# rev1-dragonfly.net
KiCad netlist of a schematic drawn in EAGLE
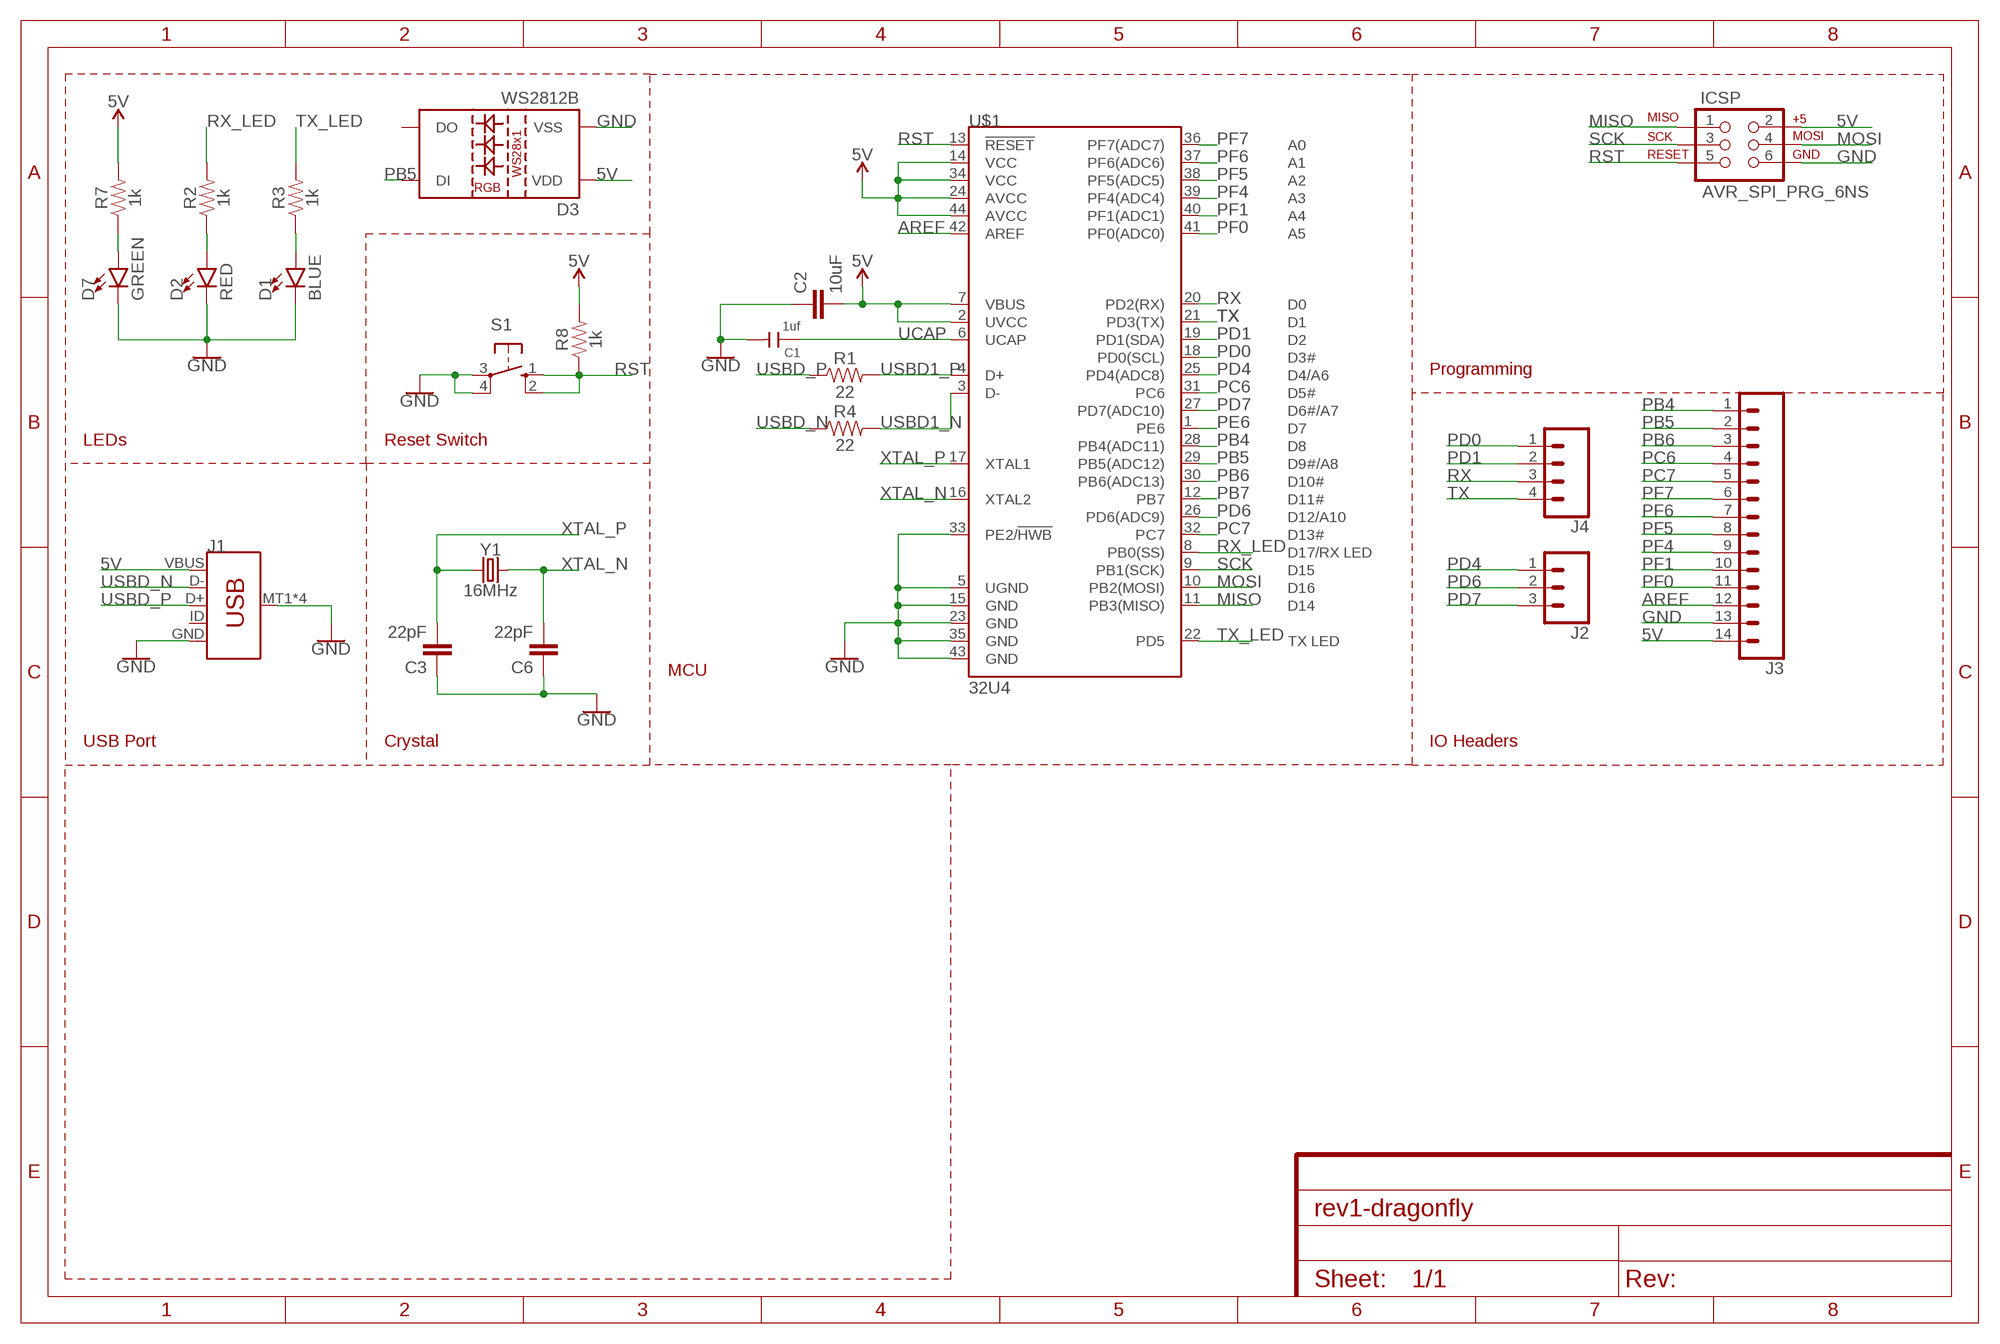
[diagram p0: schematic, sheet 1]

(export (version "E")
  (design (tool "Eeschema 10.0.6"))
  (components
    (comp (ref "C1")
      (value "1uf")
      (footprint "eagle-import:C0603")
      (fields (field (name "MPN") "CC0603KRX7R8BB105"))
      (libsource (lib "eagle-import") (part "CERAMIC-1UF-25V-10%-X7R(0603)"))
    )
    (comp (ref "C2")
      (value "10uF")
      (footprint "eagle-import:0805")
      (libsource (lib "eagle-import") (part "10UF-0805-10V-10%"))
    )
    (comp (ref "C3")
      (value "22pF")
      (footprint "eagle-import:0603")
      (libsource (lib "eagle-import") (part "22PF-0603-50V-5%"))
    )
    (comp (ref "C6")
      (value "22pF")
      (footprint "eagle-import:0603")
      (libsource (lib "eagle-import") (part "22PF-0603-50V-5%"))
    )
    (comp (ref "D1")
      (value "BLUE")
      (footprint "eagle-import:LED-0603")
      (libsource (lib "eagle-import") (part "LED-BLUE0603"))
    )
    (comp (ref "D2")
      (value "RED")
      (footprint "eagle-import:LED-0603")
      (libsource (lib "eagle-import") (part "LED-RED0603"))
    )
    (comp (ref "D3")
      (value "WS2812B")
      (footprint "eagle-import:WS2812B")
      (libsource (lib "eagle-import") (part "WS2812B"))
    )
    (comp (ref "D7")
      (value "GREEN")
      (footprint "eagle-import:LED-0603")
      (libsource (lib "eagle-import") (part "LED-GREEN0603"))
    )
    (comp (ref "ICSP")
      (value "AVR_SPI_PRG_6NS")
      (footprint "eagle-import:2X3-NS")
      (libsource (lib "eagle-import") (part "AVR_SPI_PRG_6NS"))
    )
    (comp (ref "J1")
      (value "USB_MICRO-B_SMT")
      (footprint "eagle-import:USB-MICROB")
      (libsource (lib "eagle-import") (part "USB_MICRO-B_SMT"))
    )
    (comp (ref "J2")
      (value "CONN_03")
      (footprint "eagle-import:1X03")
      (libsource (lib "eagle-import") (part "CONN_03"))
    )
    (comp (ref "J3")
      (value "CONN_14")
      (footprint "eagle-import:1X14")
      (libsource (lib "eagle-import") (part "CONN_14"))
    )
    (comp (ref "J4")
      (value "CONN_04")
      (footprint "eagle-import:1X04")
      (libsource (lib "eagle-import") (part "CONN_04"))
    )
    (comp (ref "R1")
      (value "22")
      (footprint "eagle-import:0603")
      (libsource (lib "eagle-import") (part "22OHM-0603-1/10W-1%"))
    )
    (comp (ref "R2")
      (value "1k")
      (footprint "eagle-import:0805")
      (libsource (lib "eagle-import") (part "RESISTOR0805"))
    )
    (comp (ref "R3")
      (value "1k")
      (footprint "eagle-import:0805")
      (libsource (lib "eagle-import") (part "RESISTOR0805"))
    )
    (comp (ref "R4")
      (value "22")
      (footprint "eagle-import:0603")
      (libsource (lib "eagle-import") (part "22OHM-0603-1/10W-1%"))
    )
    (comp (ref "R7")
      (value "1k")
      (footprint "eagle-import:0805")
      (libsource (lib "eagle-import") (part "RESISTOR0805"))
    )
    (comp (ref "R8")
      (value "1k")
      (footprint "eagle-import:0805")
      (libsource (lib "eagle-import") (part "RESISTOR0805"))
    )
    (comp (ref "S1")
      (value "10-XX")
      (footprint "eagle-import:B3F-10XX")
      (fields (field (name "MPN") "B3F-1000"))
      (libsource (lib "eagle-import") (part "10-XX"))
    )
    (comp (ref "U$1")
      (value "32U4")
      (footprint "eagle-import:TQFP44")
      (libsource (lib "eagle-import") (part "ATMEGA32U4TQFP-44"))
    )
    (comp (ref "Y1")
      (value "16MHz")
      (footprint "eagle-import:HC49US")
      (libsource (lib "eagle-import") (part "CRYSTAL-16MHZPTH-HC49US"))
    )
  )
  (nets
    (net (code "1") (name "/AREF") (class "Default")
      (node (ref "J3") (pin "12") (pinfunction "12_12") (pintype "passive"))
      (node (ref "U$1") (pin "42") (pinfunction "AREF_42") (pintype "bidirectional"))
    )
    (net (code "2") (name "/MISO") (class "Default")
      (node (ref "ICSP") (pin "1") (pinfunction "1_1") (pintype "passive"))
      (node (ref "U$1") (pin "11") (pinfunction "PB3(MISO)_11") (pintype "bidirectional"))
    )
    (net (code "3") (name "/MOSI") (class "Default")
      (node (ref "ICSP") (pin "4") (pinfunction "4_4") (pintype "passive"))
      (node (ref "U$1") (pin "10") (pinfunction "PB2(MOSI)_10") (pintype "bidirectional"))
    )
    (net (code "4") (name "/PB4") (class "Default")
      (node (ref "J3") (pin "1") (pinfunction "1_1") (pintype "passive"))
      (node (ref "U$1") (pin "28") (pinfunction "PB4(ADC11)_28") (pintype "bidirectional"))
    )
    (net (code "5") (name "/PB5") (class "Default")
      (node (ref "D3") (pin "4") (pinfunction "DI_4") (pintype "bidirectional"))
      (node (ref "J3") (pin "2") (pinfunction "2_2") (pintype "passive"))
      (node (ref "U$1") (pin "29") (pinfunction "PB5(ADC12)_29") (pintype "bidirectional"))
    )
    (net (code "6") (name "/PB6") (class "Default")
      (node (ref "J3") (pin "3") (pinfunction "3_3") (pintype "passive"))
      (node (ref "U$1") (pin "30") (pinfunction "PB6(ADC13)_30") (pintype "bidirectional"))
    )
    (net (code "7") (name "/PB7") (class "Default")
      (node (ref "U$1") (pin "12") (pinfunction "PB7_12") (pintype "bidirectional"))
    )
    (net (code "8") (name "/PC6") (class "Default")
      (node (ref "J3") (pin "4") (pinfunction "4_4") (pintype "passive"))
      (node (ref "U$1") (pin "31") (pinfunction "PC6_31") (pintype "bidirectional"))
    )
    (net (code "9") (name "/PC7") (class "Default")
      (node (ref "J3") (pin "5") (pinfunction "5_5") (pintype "passive"))
      (node (ref "U$1") (pin "32") (pinfunction "PC7_32") (pintype "bidirectional"))
    )
    (net (code "10") (name "/PD0") (class "Default")
      (node (ref "J4") (pin "1") (pinfunction "1_1") (pintype "passive"))
      (node (ref "U$1") (pin "18") (pinfunction "PD0(SCL)_18") (pintype "bidirectional"))
    )
    (net (code "11") (name "/PD1") (class "Default")
      (node (ref "J4") (pin "2") (pinfunction "2_2") (pintype "passive"))
      (node (ref "U$1") (pin "19") (pinfunction "PD1(SDA)_19") (pintype "bidirectional"))
    )
    (net (code "12") (name "/PD4") (class "Default")
      (node (ref "J2") (pin "1") (pinfunction "1_1") (pintype "passive"))
      (node (ref "U$1") (pin "25") (pinfunction "PD4(ADC8)_25") (pintype "bidirectional"))
    )
    (net (code "13") (name "/PD6") (class "Default")
      (node (ref "J2") (pin "2") (pinfunction "2_2") (pintype "passive"))
      (node (ref "U$1") (pin "26") (pinfunction "PD6(ADC9)_26") (pintype "bidirectional"))
    )
    (net (code "14") (name "/PD7") (class "Default")
      (node (ref "J2") (pin "3") (pinfunction "3_3") (pintype "passive"))
      (node (ref "U$1") (pin "27") (pinfunction "PD7(ADC10)_27") (pintype "bidirectional"))
    )
    (net (code "15") (name "/PE6") (class "Default")
      (node (ref "U$1") (pin "1") (pinfunction "PE6_1") (pintype "bidirectional"))
    )
    (net (code "16") (name "/PF0") (class "Default")
      (node (ref "J3") (pin "11") (pinfunction "11_11") (pintype "passive"))
      (node (ref "U$1") (pin "41") (pinfunction "PF0(ADC0)_41") (pintype "bidirectional"))
    )
    (net (code "17") (name "/PF1") (class "Default")
      (node (ref "J3") (pin "10") (pinfunction "10_10") (pintype "passive"))
      (node (ref "U$1") (pin "40") (pinfunction "PF1(ADC1)_40") (pintype "bidirectional"))
    )
    (net (code "18") (name "/PF4") (class "Default")
      (node (ref "J3") (pin "9") (pinfunction "9_9") (pintype "passive"))
      (node (ref "U$1") (pin "39") (pinfunction "PF4(ADC4)_39") (pintype "bidirectional"))
    )
    (net (code "19") (name "/PF5") (class "Default")
      (node (ref "J3") (pin "8") (pinfunction "8_8") (pintype "passive"))
      (node (ref "U$1") (pin "38") (pinfunction "PF5(ADC5)_38") (pintype "bidirectional"))
    )
    (net (code "20") (name "/PF6") (class "Default")
      (node (ref "J3") (pin "7") (pinfunction "7_7") (pintype "passive"))
      (node (ref "U$1") (pin "37") (pinfunction "PF6(ADC6)_37") (pintype "bidirectional"))
    )
    (net (code "21") (name "/PF7") (class "Default")
      (node (ref "J3") (pin "6") (pinfunction "6_6") (pintype "passive"))
      (node (ref "U$1") (pin "36") (pinfunction "PF7(ADC7)_36") (pintype "bidirectional"))
    )
    (net (code "22") (name "/RST") (class "Default")
      (node (ref "ICSP") (pin "5") (pinfunction "5_5") (pintype "passive"))
      (node (ref "R8") (pin "1") (pinfunction "1_1") (pintype "passive"))
      (node (ref "S1") (pin "1") (pinfunction "S_1") (pintype "passive"))
      (node (ref "S1") (pin "2") (pinfunction "S1_2") (pintype "passive"))
      (node (ref "U$1") (pin "13") (pinfunction "~{RESET}_13") (pintype "bidirectional"))
    )
    (net (code "23") (name "/RX") (class "Default")
      (node (ref "J4") (pin "3") (pinfunction "3_3") (pintype "passive"))
      (node (ref "U$1") (pin "20") (pinfunction "PD2(RX)_20") (pintype "bidirectional"))
    )
    (net (code "24") (name "/RX_LED") (class "Default")
      (node (ref "R2") (pin "2") (pinfunction "2_2") (pintype "passive"))
      (node (ref "U$1") (pin "8") (pinfunction "PB0(SS)_8") (pintype "bidirectional"))
    )
    (net (code "25") (name "/SCK") (class "Default")
      (node (ref "ICSP") (pin "3") (pinfunction "3_3") (pintype "passive"))
      (node (ref "U$1") (pin "9") (pinfunction "PB1(SCK)_9") (pintype "bidirectional"))
    )
    (net (code "26") (name "/TX") (class "Default")
      (node (ref "J4") (pin "4") (pinfunction "4_4") (pintype "passive"))
      (node (ref "U$1") (pin "21") (pinfunction "PD3(TX)_21") (pintype "bidirectional"))
    )
    (net (code "27") (name "/TX_LED") (class "Default")
      (node (ref "R3") (pin "2") (pinfunction "2_2") (pintype "passive"))
      (node (ref "U$1") (pin "22") (pinfunction "PD5_22") (pintype "bidirectional"))
    )
    (net (code "28") (name "/UCAP") (class "Default")
      (node (ref "C1") (pin "1") (pinfunction "1_1") (pintype "passive"))
      (node (ref "U$1") (pin "6") (pinfunction "UCAP_6") (pintype "bidirectional"))
    )
    (net (code "29") (name "/USBD1_N") (class "Default")
      (node (ref "R4") (pin "2") (pinfunction "2_2") (pintype "passive"))
      (node (ref "U$1") (pin "3") (pinfunction "D-_3") (pintype "bidirectional"))
    )
    (net (code "30") (name "/USBD1_P") (class "Default")
      (node (ref "R1") (pin "2") (pinfunction "2_2") (pintype "passive"))
      (node (ref "U$1") (pin "4") (pinfunction "D+_4") (pintype "bidirectional"))
    )
    (net (code "31") (name "/USBD_N") (class "Default")
      (node (ref "J1") (pin "D-") (pinfunction "D-_D-") (pintype "bidirectional"))
      (node (ref "R4") (pin "1") (pinfunction "1_1") (pintype "passive"))
    )
    (net (code "32") (name "/USBD_P") (class "Default")
      (node (ref "J1") (pin "D+") (pinfunction "D+_D+") (pintype "bidirectional"))
      (node (ref "R1") (pin "1") (pinfunction "1_1") (pintype "passive"))
    )
    (net (code "33") (name "/XTAL_N") (class "Default")
      (node (ref "C6") (pin "2") (pinfunction "2_2") (pintype "passive"))
      (node (ref "U$1") (pin "16") (pinfunction "XTAL2_16") (pintype "bidirectional"))
      (node (ref "Y1") (pin "2") (pinfunction "2_2") (pintype "passive"))
    )
    (net (code "34") (name "/XTAL_P") (class "Default")
      (node (ref "C3") (pin "2") (pinfunction "2_2") (pintype "passive"))
      (node (ref "U$1") (pin "17") (pinfunction "XTAL1_17") (pintype "bidirectional"))
      (node (ref "Y1") (pin "1") (pinfunction "1_1") (pintype "passive"))
    )
    (net (code "35") (name "5V") (class "Default")
      (node (ref "C2") (pin "2") (pinfunction "2_2") (pintype "passive"))
      (node (ref "D3") (pin "1") (pinfunction "VDD_1") (pintype "bidirectional"))
      (node (ref "ICSP") (pin "2") (pinfunction "2_2") (pintype "passive"))
      (node (ref "J1") (pin "VBUS") (pinfunction "VBUS_VBUS") (pintype "power_in"))
      (node (ref "J3") (pin "14") (pinfunction "14_14") (pintype "passive"))
      (node (ref "R7") (pin "2") (pinfunction "2_2") (pintype "passive"))
      (node (ref "R8") (pin "2") (pinfunction "2_2") (pintype "passive"))
      (node (ref "U$1") (pin "14") (pinfunction "VCC_14") (pintype "bidirectional"))
      (node (ref "U$1") (pin "2") (pinfunction "UVCC_2") (pintype "bidirectional"))
      (node (ref "U$1") (pin "24") (pinfunction "AVCC_24") (pintype "bidirectional"))
      (node (ref "U$1") (pin "34") (pinfunction "VCC_34") (pintype "bidirectional"))
      (node (ref "U$1") (pin "44") (pinfunction "AVCC_44") (pintype "bidirectional"))
      (node (ref "U$1") (pin "7") (pinfunction "VBUS_7") (pintype "bidirectional"))
    )
    (net (code "36") (name "GND") (class "Default")
      (node (ref "C1") (pin "2") (pinfunction "2_2") (pintype "passive"))
      (node (ref "C2") (pin "1") (pinfunction "1_1") (pintype "passive"))
      (node (ref "C3") (pin "1") (pinfunction "1_1") (pintype "passive"))
      (node (ref "C6") (pin "1") (pinfunction "1_1") (pintype "passive"))
      (node (ref "D1") (pin "C") (pinfunction "C_C") (pintype "passive"))
      (node (ref "D2") (pin "C") (pinfunction "C_C") (pintype "passive"))
      (node (ref "D3") (pin "3") (pinfunction "VSS_3") (pintype "bidirectional"))
      (node (ref "D7") (pin "C") (pinfunction "C_C") (pintype "passive"))
      (node (ref "ICSP") (pin "6") (pinfunction "6_6") (pintype "passive"))
      (node (ref "J1") (pin "GND") (pinfunction "GND_GND") (pintype "power_in"))
      (node (ref "J1") (pin "MT1") (pinfunction "SHIELD_MT1") (pintype "bidirectional"))
      (node (ref "J1") (pin "MT2") (pinfunction "SHIELD_MT2") (pintype "bidirectional"))
      (node (ref "J1") (pin "P$1") (pinfunction "SHIELD_P$1") (pintype "bidirectional"))
      (node (ref "J1") (pin "P$2") (pinfunction "SHIELD_P$2") (pintype "bidirectional"))
      (node (ref "J3") (pin "13") (pinfunction "13_13") (pintype "passive"))
      (node (ref "S1") (pin "3") (pinfunction "P_3") (pintype "passive"))
      (node (ref "S1") (pin "4") (pinfunction "P1_4") (pintype "passive"))
      (node (ref "U$1") (pin "15") (pinfunction "GND_15") (pintype "bidirectional"))
      (node (ref "U$1") (pin "23") (pinfunction "GND_23") (pintype "bidirectional"))
      (node (ref "U$1") (pin "33") (pinfunction "PE2/~{HWB}_33") (pintype "bidirectional"))
      (node (ref "U$1") (pin "35") (pinfunction "GND_35") (pintype "bidirectional"))
      (node (ref "U$1") (pin "43") (pinfunction "GND_43") (pintype "bidirectional"))
      (node (ref "U$1") (pin "5") (pinfunction "UGND_5") (pintype "bidirectional"))
    )
    (net (code "37") (name "Net-(D1-PadA)") (class "Default")
      (node (ref "D1") (pin "A") (pinfunction "A_A") (pintype "passive"))
      (node (ref "R3") (pin "1") (pinfunction "1_1") (pintype "passive"))
    )
    (net (code "38") (name "Net-(D2-PadA)") (class "Default")
      (node (ref "D2") (pin "A") (pinfunction "A_A") (pintype "passive"))
      (node (ref "R2") (pin "1") (pinfunction "1_1") (pintype "passive"))
    )
    (net (code "39") (name "Net-(D7-PadA)") (class "Default")
      (node (ref "D7") (pin "A") (pinfunction "A_A") (pintype "passive"))
      (node (ref "R7") (pin "1") (pinfunction "1_1") (pintype "passive"))
    )
    (net (code "40") (name "unconnected-(D3-DO-Pad2)") (class "Default")
      (node (ref "D3") (pin "2") (pinfunction "DO_2") (pintype "bidirectional"))
    )
    (net (code "41") (name "unconnected-(J1-PadID)") (class "Default")
      (node (ref "J1") (pin "ID") (pinfunction "ID_ID") (pintype "bidirectional"))
    )
  )
)
